# GENN0005_Flatsat_ConnectorFootprints.net
KiCad netlist of a schematic drawn in Altium Designer
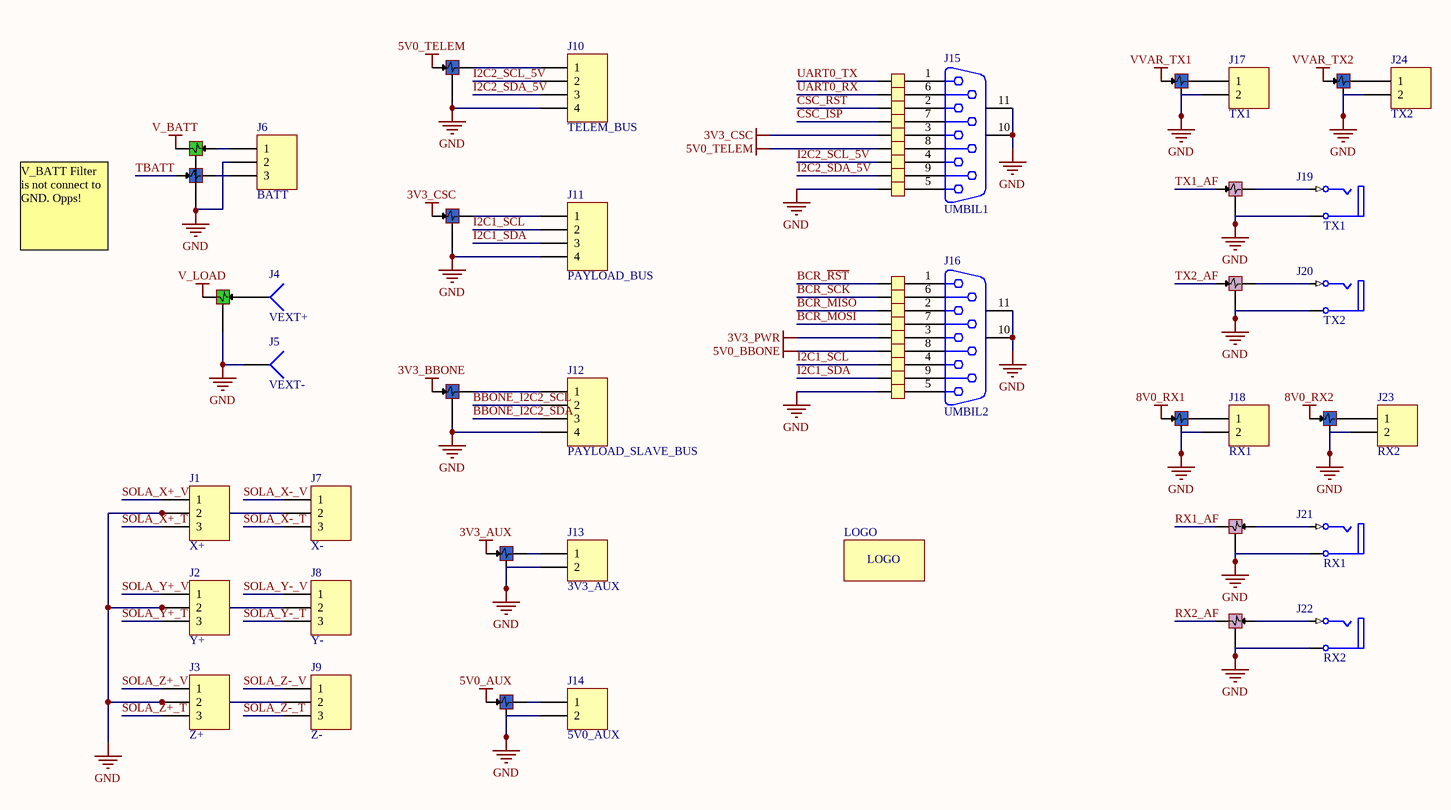
[diagram p0: GENN0005 Flatsat ConnectorFootprints.SchDoc]

(export (version "E")
  (design (tool "Eeschema 10.0.6"))
  (components
    (comp (ref "F1")
      (value "FilterSola")
      (footprint "FILTERSOLA")
      (libsource (lib "FlatBoards") (part "FilterSola"))
    )
    (comp (ref "F2")
      (value "FilterPwr")
      (footprint "FILTERPWR")
      (libsource (lib "FlatBoards") (part "FilterPwr"))
    )
    (comp (ref "F3")
      (value "FilterPwr")
      (footprint "FILTERPWR")
      (libsource (lib "FlatBoards") (part "FilterPwr"))
    )
    (comp (ref "F4")
      (value "FilterPwr")
      (footprint "FILTERPWR")
      (libsource (lib "FlatBoards") (part "FilterPwr"))
    )
    (comp (ref "F5")
      (value "FilterPwr")
      (footprint "FILTERPWR")
      (libsource (lib "FlatBoards") (part "FilterPwr"))
    )
    (comp (ref "F6")
      (value "FilterPwr")
      (footprint "FILTERPWR")
      (libsource (lib "FlatBoards") (part "FilterPwr"))
    )
    (comp (ref "F7")
      (value "FilterPwr")
      (footprint "FILTERPWR")
      (libsource (lib "FlatBoards") (part "FilterPwr"))
    )
    (comp (ref "F8")
      (value "FilterPwr")
      (footprint "FILTERPWR")
      (libsource (lib "FlatBoards") (part "FilterPwr"))
    )
    (comp (ref "F9") (value "Filter") (footprint "Filter") (libsource (lib "FlatBoards") (part "Filter")))
    (comp (ref "F10") (value "Filter") (footprint "Filter") (libsource (lib "FlatBoards") (part "Filter")))
    (comp (ref "F11") (value "Filter") (footprint "Filter") (libsource (lib "") (part "Filter_1")))
    (comp (ref "F12") (value "Filter") (footprint "Filter") (libsource (lib "") (part "Filter_1")))
    (comp (ref "F13")
      (value "FilterPwr")
      (footprint "FILTERPWR")
      (libsource (lib "FlatBoards") (part "FilterPwr"))
    )
    (comp (ref "F14")
      (value "FilterPwr")
      (footprint "FILTERPWR")
      (libsource (lib "FlatBoards") (part "FilterPwr"))
    )
    (comp (ref "F98")
      (value "FilterPwr")
      (footprint "FILTERPWR")
      (libsource (lib "FlatBoards") (part "FilterPwr"))
    )
    (comp (ref "F99")
      (value "FilterSola")
      (footprint "FILTERSOLA")
      (libsource (lib "FlatBoards") (part "FilterSola"))
    )
    (comp (ref "J1")
      (value "X+")
      (footprint "SCREW3")
      (description "Header, 3-Pin")
      (fields (field (name "PUBLISHER") "Altium Limited"))
      (libsource (lib "Miscellaneous Connectors") (part "Header 3"))
    )
    (comp (ref "J2")
      (value "Y+")
      (footprint "SCREW3")
      (description "Header, 3-Pin")
      (fields (field (name "PUBLISHER") "Altium Limited"))
      (libsource (lib "Miscellaneous Connectors") (part "Header 3"))
    )
    (comp (ref "J3")
      (value "Z+")
      (footprint "SCREW3")
      (description "Header, 3-Pin")
      (fields (field (name "PUBLISHER") "Altium Limited"))
      (libsource (lib "Miscellaneous Connectors") (part "Header 3"))
    )
    (comp (ref "J4")
      (value "VEXT+")
      (footprint "4MM_BANANA")
      (description "Socket")
      (fields (field (name "PUBLISHER") "Altium Limited"))
      (libsource (lib "Miscellaneous Connectors") (part "Socket"))
    )
    (comp (ref "J5")
      (value "VEXT-")
      (footprint "4MM_BANANA")
      (description "Socket")
      (fields (field (name "PUBLISHER") "Altium Limited"))
      (libsource (lib "Miscellaneous Connectors") (part "Socket"))
    )
    (comp (ref "J6")
      (value "BATT")
      (footprint "SCREW3")
      (description "Header, 3-Pin")
      (fields (field (name "PUBLISHER") "Altium Limited"))
      (libsource (lib "Miscellaneous Connectors") (part "Header 3"))
    )
    (comp (ref "J7")
      (value "X-")
      (footprint "SCREW3")
      (description "Header, 3-Pin")
      (fields (field (name "PUBLISHER") "Altium Limited"))
      (libsource (lib "Miscellaneous Connectors") (part "Header 3"))
    )
    (comp (ref "J8")
      (value "Y-")
      (footprint "SCREW3")
      (description "Header, 3-Pin")
      (fields (field (name "PUBLISHER") "Altium Limited"))
      (libsource (lib "Miscellaneous Connectors") (part "Header 3"))
    )
    (comp (ref "J9")
      (value "Z-")
      (footprint "SCREW3")
      (description "Header, 3-Pin")
      (fields (field (name "PUBLISHER") "Altium Limited"))
      (libsource (lib "Miscellaneous Connectors") (part "Header 3"))
    )
    (comp (ref "J10")
      (value "TELEM_BUS")
      (footprint "HDR1X4")
      (description "Header, 4-Pin")
      (fields (field (name "PUBLISHER") "Altium Limited"))
      (libsource (lib "Miscellaneous Connectors") (part "Header 4"))
    )
    (comp (ref "J11")
      (value "PAYLOAD_BUS")
      (footprint "HDR1X4")
      (description "Header, 4-Pin")
      (fields (field (name "PUBLISHER") "Altium Limited"))
      (libsource (lib "Miscellaneous Connectors") (part "Header 4"))
    )
    (comp (ref "J12")
      (value "PAYLOAD_SLAVE_BUS")
      (footprint "HDR1X4")
      (description "Header, 4-Pin")
      (fields (field (name "PUBLISHER") "Altium Limited"))
      (libsource (lib "Miscellaneous Connectors") (part "Header 4"))
    )
    (comp (ref "J13")
      (value "3V3_AUX")
      (footprint "SCREW2")
      (description "Header, 2-Pin")
      (fields (field (name "PUBLISHER") "Altium Limited"))
      (libsource (lib "Miscellaneous Connectors") (part "Header 2"))
    )
    (comp (ref "J14")
      (value "5V0_AUX")
      (footprint "SCREW2")
      (description "Header, 2-Pin")
      (fields (field (name "PUBLISHER") "Altium Limited"))
      (libsource (lib "Miscellaneous Connectors") (part "Header 2"))
    )
    (comp (ref "J15")
      (value "UMBIL1")
      (footprint "D9 - temp")
      (description "Receptacle Assembly, 9 Position, Right Angle")
      (fields (field (name "PUBLISHER") "Altium Limited"))
      (libsource (lib "Miscellaneous Connectors") (part "D Connector 9"))
    )
    (comp (ref "J16")
      (value "UMBIL2")
      (footprint "D9 - temp")
      (description "Receptacle Assembly, 9 Position, Right Angle")
      (fields (field (name "PUBLISHER") "Altium Limited"))
      (libsource (lib "Miscellaneous Connectors") (part "D Connector 9"))
    )
    (comp (ref "J17")
      (value "TX1")
      (footprint "SCREW2")
      (description "Header, 2-Pin")
      (fields (field (name "PUBLISHER") "Altium Limited"))
      (libsource (lib "Miscellaneous Connectors") (part "Header 2"))
    )
    (comp (ref "J18")
      (value "RX1")
      (footprint "SCREW2")
      (description "Header, 2-Pin")
      (fields (field (name "PUBLISHER") "Altium Limited"))
      (libsource (lib "Miscellaneous Connectors") (part "Header 2"))
    )
    (comp (ref "J19")
      (value "TX1")
      (footprint "R/A RCA")
      (description "RCA Phono Jack, Right Angle, Thru-Hole, Snap-In")
      (fields (field (name "PUBLISHER") "Altium Limited"))
      (libsource (lib "Miscellaneous Connectors") (part "RCA"))
    )
    (comp (ref "J20")
      (value "TX2")
      (footprint "R/A RCA")
      (description "RCA Phono Jack, Right Angle, Thru-Hole, Snap-In")
      (fields (field (name "PUBLISHER") "Altium Limited"))
      (libsource (lib "Miscellaneous Connectors") (part "RCA"))
    )
    (comp (ref "J21")
      (value "RX1")
      (footprint "R/A RCA")
      (description "RCA Phono Jack, Right Angle, Thru-Hole, Snap-In")
      (fields (field (name "PUBLISHER") "Altium Limited"))
      (libsource (lib "Miscellaneous Connectors") (part "RCA"))
    )
    (comp (ref "J22")
      (value "RX2")
      (footprint "R/A RCA")
      (description "RCA Phono Jack, Right Angle, Thru-Hole, Snap-In")
      (fields (field (name "PUBLISHER") "Altium Limited"))
      (libsource (lib "Miscellaneous Connectors") (part "RCA"))
    )
    (comp (ref "J23")
      (value "RX2")
      (footprint "SCREW2")
      (description "Header, 2-Pin")
      (fields (field (name "PUBLISHER") "Altium Limited"))
      (libsource (lib "Miscellaneous Connectors") (part "Header 2"))
    )
    (comp (ref "J24")
      (value "TX2")
      (footprint "SCREW2")
      (description "Header, 2-Pin")
      (fields (field (name "PUBLISHER") "Altium Limited"))
      (libsource (lib "Miscellaneous Connectors") (part "Header 2"))
    )
    (comp (ref "LOGO") (value "~") (footprint "LOGO") (libsource (lib "FlatBoards") (part "LOGO")))
    (comp (ref "P185") (value "Jumper") (footprint "Jumper") (libsource (lib "FlatBoards") (part "Jumper")))
    (comp (ref "P186") (value "Jumper") (footprint "Jumper") (libsource (lib "FlatBoards") (part "Jumper")))
    (comp (ref "P187") (value "Jumper") (footprint "Jumper") (libsource (lib "FlatBoards") (part "Jumper")))
    (comp (ref "P188") (value "Jumper") (footprint "Jumper") (libsource (lib "FlatBoards") (part "Jumper")))
    (comp (ref "P189") (value "Jumper") (footprint "Jumper") (libsource (lib "FlatBoards") (part "Jumper")))
    (comp (ref "P190") (value "Jumper") (footprint "Jumper") (libsource (lib "FlatBoards") (part "Jumper")))
    (comp (ref "P191") (value "Jumper") (footprint "Jumper") (libsource (lib "FlatBoards") (part "Jumper")))
    (comp (ref "P192") (value "Jumper") (footprint "Jumper") (libsource (lib "FlatBoards") (part "Jumper")))
    (comp (ref "P193") (value "Jumper") (footprint "Jumper") (libsource (lib "FlatBoards") (part "Jumper")))
    (comp (ref "P194") (value "Jumper") (footprint "Jumper") (libsource (lib "FlatBoards") (part "Jumper")))
    (comp (ref "P195") (value "Jumper") (footprint "Jumper") (libsource (lib "FlatBoards") (part "Jumper")))
    (comp (ref "P196") (value "Jumper") (footprint "Jumper") (libsource (lib "FlatBoards") (part "Jumper")))
    (comp (ref "P197") (value "Jumper") (footprint "Jumper") (libsource (lib "FlatBoards") (part "Jumper")))
    (comp (ref "P198") (value "Jumper") (footprint "Jumper") (libsource (lib "FlatBoards") (part "Jumper")))
    (comp (ref "P199") (value "Jumper") (footprint "Jumper") (libsource (lib "FlatBoards") (part "Jumper")))
    (comp (ref "P200") (value "Jumper") (footprint "Jumper") (libsource (lib "FlatBoards") (part "Jumper")))
    (comp (ref "P201") (value "Jumper") (footprint "Jumper") (libsource (lib "FlatBoards") (part "Jumper")))
    (comp (ref "P202") (value "Jumper") (footprint "Jumper") (libsource (lib "FlatBoards") (part "Jumper")))
  )
  (nets
    (net (code "1") (name "/BBONE_I2C2_SCL") (class "Default")
      (node (ref "J12") (pin "2") (pinfunction "2_2") (pintype "passive"))
    )
    (net (code "2") (name "/BBONE_I2C2_SDA") (class "Default")
      (node (ref "J12") (pin "3") (pinfunction "3_3") (pintype "passive"))
    )
    (net (code "3") (name "/BCR_MISO") (class "Default") (node (ref "P196") (pin "1") (pintype "passive")))
    (net (code "4") (name "/BCR_MOSI") (class "Default") (node (ref "P197") (pin "1") (pintype "passive")))
    (net (code "5") (name "/BCR_SCK") (class "Default") (node (ref "P195") (pin "1") (pintype "passive")))
    (net (code "6") (name "/BCR_~{RST}") (class "Default") (node (ref "P194") (pin "1") (pintype "passive")))
    (net (code "7") (name "/CSC_ISP") (class "Default") (node (ref "P188") (pin "1") (pintype "passive")))
    (net (code "8") (name "/CSC_RST") (class "Default") (node (ref "P187") (pin "1") (pintype "passive")))
    (net (code "9") (name "/I2C1_SCL") (class "Default")
      (node (ref "J11") (pin "2") (pinfunction "2_2") (pintype "passive"))
      (node (ref "P200") (pin "1") (pintype "passive"))
    )
    (net (code "10") (name "/I2C1_SDA") (class "Default")
      (node (ref "J11") (pin "3") (pinfunction "3_3") (pintype "passive"))
      (node (ref "P201") (pin "1") (pintype "passive"))
    )
    (net (code "11") (name "/I2C2_SCL_5V") (class "Default")
      (node (ref "J10") (pin "2") (pinfunction "2_2") (pintype "passive"))
      (node (ref "P191") (pin "1") (pintype "passive"))
    )
    (net (code "12") (name "/I2C2_SDA_5V") (class "Default")
      (node (ref "J10") (pin "3") (pinfunction "3_3") (pintype "passive"))
      (node (ref "P192") (pin "1") (pintype "passive"))
    )
    (net (code "13") (name "/RX1_AF") (class "Default") (node (ref "F11") (pin "2") (pintype "passive")))
    (net (code "14") (name "/RX2_AF") (class "Default") (node (ref "F12") (pin "2") (pintype "passive")))
    (net (code "15") (name "/SOLA_X+_T") (class "Default")
      (node (ref "J1") (pin "3") (pinfunction "3_3") (pintype "passive"))
    )
    (net (code "16") (name "/SOLA_X+_V") (class "Default")
      (node (ref "J1") (pin "1") (pinfunction "1_1") (pintype "passive"))
    )
    (net (code "17") (name "/SOLA_X-_T") (class "Default")
      (node (ref "J7") (pin "3") (pinfunction "3_3") (pintype "passive"))
    )
    (net (code "18") (name "/SOLA_X-_V") (class "Default")
      (node (ref "J7") (pin "1") (pinfunction "1_1") (pintype "passive"))
    )
    (net (code "19") (name "/SOLA_Y+_T") (class "Default")
      (node (ref "J2") (pin "3") (pinfunction "3_3") (pintype "passive"))
    )
    (net (code "20") (name "/SOLA_Y+_V") (class "Default")
      (node (ref "J2") (pin "1") (pinfunction "1_1") (pintype "passive"))
    )
    (net (code "21") (name "/SOLA_Y-_T") (class "Default")
      (node (ref "J8") (pin "3") (pinfunction "3_3") (pintype "passive"))
    )
    (net (code "22") (name "/SOLA_Y-_V") (class "Default")
      (node (ref "J8") (pin "1") (pinfunction "1_1") (pintype "passive"))
    )
    (net (code "23") (name "/SOLA_Z+_T") (class "Default")
      (node (ref "J3") (pin "3") (pinfunction "3_3") (pintype "passive"))
    )
    (net (code "24") (name "/SOLA_Z+_V") (class "Default")
      (node (ref "J3") (pin "1") (pinfunction "1_1") (pintype "passive"))
    )
    (net (code "25") (name "/SOLA_Z-_T") (class "Default")
      (node (ref "J9") (pin "3") (pinfunction "3_3") (pintype "passive"))
    )
    (net (code "26") (name "/SOLA_Z-_V") (class "Default")
      (node (ref "J9") (pin "1") (pinfunction "1_1") (pintype "passive"))
    )
    (net (code "27") (name "/TBATT") (class "Default") (node (ref "F98") (pin "1") (pintype "passive")))
    (net (code "28") (name "/TX1_AF") (class "Default") (node (ref "F9") (pin "1") (pintype "passive")))
    (net (code "29") (name "/TX2_AF") (class "Default") (node (ref "F10") (pin "1") (pintype "passive")))
    (net (code "30") (name "/UART0_RX") (class "Default") (node (ref "P186") (pin "1") (pintype "passive")))
    (net (code "31") (name "/UART0_TX") (class "Default") (node (ref "P185") (pin "1") (pintype "passive")))
    (net (code "32") (name "3V3_AUX") (class "Default") (node (ref "F5") (pin "1") (pintype "passive")))
    (net (code "33") (name "3V3_BBONE") (class "Default") (node (ref "F4") (pin "1") (pintype "passive")))
    (net (code "34") (name "3V3_CSC") (class "Default")
      (node (ref "F3") (pin "1") (pintype "passive"))
      (node (ref "P189") (pin "1") (pintype "passive"))
    )
    (net (code "35") (name "3V3_PWR") (class "Default") (node (ref "P198") (pin "1") (pintype "passive")))
    (net (code "36") (name "5V0_AUX") (class "Default") (node (ref "F6") (pin "1") (pintype "passive")))
    (net (code "37") (name "5V0_BBONE") (class "Default") (node (ref "P199") (pin "1") (pintype "passive")))
    (net (code "38") (name "5V0_TELEM") (class "Default")
      (node (ref "F2") (pin "1") (pintype "passive"))
      (node (ref "P190") (pin "1") (pintype "passive"))
    )
    (net (code "39") (name "8V0_RX1") (class "Default") (node (ref "F8") (pin "1") (pintype "passive")))
    (net (code "40") (name "8V0_RX2") (class "Default") (node (ref "F13") (pin "1") (pintype "passive")))
    (net (code "41") (name "GND") (class "Default")
      (node (ref "F1") (pin "3") (pintype "passive"))
      (node (ref "F10") (pin "3") (pintype "passive"))
      (node (ref "F11") (pin "3") (pintype "passive"))
      (node (ref "F12") (pin "3") (pintype "passive"))
      (node (ref "F13") (pin "3") (pintype "passive"))
      (node (ref "F14") (pin "3") (pintype "passive"))
      (node (ref "F2") (pin "3") (pintype "passive"))
      (node (ref "F3") (pin "3") (pintype "passive"))
      (node (ref "F4") (pin "3") (pintype "passive"))
      (node (ref "F5") (pin "3") (pintype "passive"))
      (node (ref "F6") (pin "3") (pintype "passive"))
      (node (ref "F7") (pin "3") (pintype "passive"))
      (node (ref "F8") (pin "3") (pintype "passive"))
      (node (ref "F9") (pin "3") (pintype "passive"))
      (node (ref "F98") (pin "3") (pintype "passive"))
      (node (ref "J1") (pin "2") (pinfunction "2_2") (pintype "passive"))
      (node (ref "J10") (pin "4") (pinfunction "4_4") (pintype "passive"))
      (node (ref "J11") (pin "4") (pinfunction "4_4") (pintype "passive"))
      (node (ref "J12") (pin "4") (pinfunction "4_4") (pintype "passive"))
      (node (ref "J13") (pin "2") (pinfunction "2_2") (pintype "passive"))
      (node (ref "J14") (pin "2") (pinfunction "2_2") (pintype "passive"))
      (node (ref "J15") (pin "10") (pinfunction "MH1_10") (pintype "passive"))
      (node (ref "J15") (pin "11") (pinfunction "MH2_11") (pintype "passive"))
      (node (ref "J16") (pin "10") (pinfunction "MH1_10") (pintype "passive"))
      (node (ref "J16") (pin "11") (pinfunction "MH2_11") (pintype "passive"))
      (node (ref "J17") (pin "2") (pinfunction "2_2") (pintype "passive"))
      (node (ref "J18") (pin "2") (pinfunction "2_2") (pintype "passive"))
      (node (ref "J19") (pin "1A") (pinfunction "Ground_1A") (pintype "power_in"))
      (node (ref "J2") (pin "2") (pinfunction "2_2") (pintype "passive"))
      (node (ref "J20") (pin "1A") (pinfunction "Ground_1A") (pintype "power_in"))
      (node (ref "J21") (pin "1A") (pinfunction "Ground_1A") (pintype "power_in"))
      (node (ref "J22") (pin "1A") (pinfunction "Ground_1A") (pintype "power_in"))
      (node (ref "J23") (pin "2") (pinfunction "2_2") (pintype "passive"))
      (node (ref "J24") (pin "2") (pinfunction "2_2") (pintype "passive"))
      (node (ref "J3") (pin "2") (pinfunction "2_2") (pintype "passive"))
      (node (ref "J5") (pin "1") (pinfunction "1_1") (pintype "passive"))
      (node (ref "J6") (pin "2") (pinfunction "2_2") (pintype "passive"))
      (node (ref "J7") (pin "2") (pinfunction "2_2") (pintype "passive"))
      (node (ref "J8") (pin "2") (pinfunction "2_2") (pintype "passive"))
      (node (ref "J9") (pin "2") (pinfunction "2_2") (pintype "passive"))
      (node (ref "P193") (pin "1") (pintype "passive"))
      (node (ref "P202") (pin "1") (pintype "passive"))
    )
    (net (code "42") (name "Net-(F1-Pad1)") (class "Default")
      (node (ref "F1") (pin "1") (pintype "passive"))
      (node (ref "J4") (pin "1") (pinfunction "1_1") (pintype "passive"))
    )
    (net (code "43") (name "Net-(F2-Pad2)") (class "Default")
      (node (ref "F2") (pin "2") (pintype "passive"))
      (node (ref "J10") (pin "1") (pinfunction "1_1") (pintype "passive"))
    )
    (net (code "44") (name "Net-(F3-Pad2)") (class "Default")
      (node (ref "F3") (pin "2") (pintype "passive"))
      (node (ref "J11") (pin "1") (pinfunction "1_1") (pintype "passive"))
    )
    (net (code "45") (name "Net-(F4-Pad2)") (class "Default")
      (node (ref "F4") (pin "2") (pintype "passive"))
      (node (ref "J12") (pin "1") (pinfunction "1_1") (pintype "passive"))
    )
    (net (code "46") (name "Net-(F5-Pad2)") (class "Default")
      (node (ref "F5") (pin "2") (pintype "passive"))
      (node (ref "J13") (pin "1") (pinfunction "1_1") (pintype "passive"))
    )
    (net (code "47") (name "Net-(F6-Pad2)") (class "Default")
      (node (ref "F6") (pin "2") (pintype "passive"))
      (node (ref "J14") (pin "1") (pinfunction "1_1") (pintype "passive"))
    )
    (net (code "48") (name "Net-(F7-Pad2)") (class "Default")
      (node (ref "F7") (pin "2") (pintype "passive"))
      (node (ref "J17") (pin "1") (pinfunction "1_1") (pintype "passive"))
    )
    (net (code "49") (name "Net-(F8-Pad2)") (class "Default")
      (node (ref "F8") (pin "2") (pintype "passive"))
      (node (ref "J18") (pin "1") (pinfunction "1_1") (pintype "passive"))
    )
    (net (code "50") (name "Net-(F13-Pad2)") (class "Default")
      (node (ref "F13") (pin "2") (pintype "passive"))
      (node (ref "J23") (pin "1") (pinfunction "1_1") (pintype "passive"))
    )
    (net (code "51") (name "Net-(F14-Pad2)") (class "Default")
      (node (ref "F14") (pin "2") (pintype "passive"))
      (node (ref "J24") (pin "1") (pinfunction "1_1") (pintype "passive"))
    )
    (net (code "52") (name "Net-(F98-Pad2)") (class "Default")
      (node (ref "F98") (pin "2") (pintype "passive"))
      (node (ref "J6") (pin "3") (pinfunction "3_3") (pintype "passive"))
    )
    (net (code "53") (name "Net-(F99-Pad1)") (class "Default")
      (node (ref "F99") (pin "1") (pintype "passive"))
      (node (ref "J6") (pin "1") (pinfunction "1_1") (pintype "passive"))
    )
    (net (code "54") (name "Net-(J15-Pad1)") (class "Default")
      (node (ref "J15") (pin "1") (pinfunction "1_1") (pintype "passive"))
      (node (ref "P185") (pin "2") (pintype "passive"))
    )
    (net (code "55") (name "Net-(J15-Pad2)") (class "Default")
      (node (ref "J15") (pin "2") (pinfunction "2_2") (pintype "passive"))
      (node (ref "P187") (pin "2") (pintype "passive"))
    )
    (net (code "56") (name "Net-(J15-Pad3)") (class "Default")
      (node (ref "J15") (pin "3") (pinfunction "3_3") (pintype "passive"))
      (node (ref "P189") (pin "2") (pintype "passive"))
    )
    (net (code "57") (name "Net-(J15-Pad4)") (class "Default")
      (node (ref "J15") (pin "4") (pinfunction "4_4") (pintype "passive"))
      (node (ref "P191") (pin "2") (pintype "passive"))
    )
    (net (code "58") (name "Net-(J15-Pad5)") (class "Default")
      (node (ref "J15") (pin "5") (pinfunction "5_5") (pintype "passive"))
      (node (ref "P193") (pin "2") (pintype "passive"))
    )
    (net (code "59") (name "Net-(J15-Pad6)") (class "Default")
      (node (ref "J15") (pin "6") (pinfunction "6_6") (pintype "passive"))
      (node (ref "P186") (pin "2") (pintype "passive"))
    )
    (net (code "60") (name "Net-(J15-Pad7)") (class "Default")
      (node (ref "J15") (pin "7") (pinfunction "7_7") (pintype "passive"))
      (node (ref "P188") (pin "2") (pintype "passive"))
    )
    (net (code "61") (name "Net-(J15-Pad8)") (class "Default")
      (node (ref "J15") (pin "8") (pinfunction "8_8") (pintype "passive"))
      (node (ref "P190") (pin "2") (pintype "passive"))
    )
    (net (code "62") (name "Net-(J15-Pad9)") (class "Default")
      (node (ref "J15") (pin "9") (pinfunction "9_9") (pintype "passive"))
      (node (ref "P192") (pin "2") (pintype "passive"))
    )
    (net (code "63") (name "Net-(J16-Pad1)") (class "Default")
      (node (ref "J16") (pin "1") (pinfunction "1_1") (pintype "passive"))
      (node (ref "P194") (pin "2") (pintype "passive"))
    )
    (net (code "64") (name "Net-(J16-Pad2)") (class "Default")
      (node (ref "J16") (pin "2") (pinfunction "2_2") (pintype "passive"))
      (node (ref "P196") (pin "2") (pintype "passive"))
    )
    (net (code "65") (name "Net-(J16-Pad3)") (class "Default")
      (node (ref "J16") (pin "3") (pinfunction "3_3") (pintype "passive"))
      (node (ref "P198") (pin "2") (pintype "passive"))
    )
    (net (code "66") (name "Net-(J16-Pad4)") (class "Default")
      (node (ref "J16") (pin "4") (pinfunction "4_4") (pintype "passive"))
      (node (ref "P200") (pin "2") (pintype "passive"))
    )
    (net (code "67") (name "Net-(J16-Pad5)") (class "Default")
      (node (ref "J16") (pin "5") (pinfunction "5_5") (pintype "passive"))
      (node (ref "P202") (pin "2") (pintype "passive"))
    )
    (net (code "68") (name "Net-(J16-Pad6)") (class "Default")
      (node (ref "J16") (pin "6") (pinfunction "6_6") (pintype "passive"))
      (node (ref "P195") (pin "2") (pintype "passive"))
    )
    (net (code "69") (name "Net-(J16-Pad7)") (class "Default")
      (node (ref "J16") (pin "7") (pinfunction "7_7") (pintype "passive"))
      (node (ref "P197") (pin "2") (pintype "passive"))
    )
    (net (code "70") (name "Net-(J16-Pad8)") (class "Default")
      (node (ref "J16") (pin "8") (pinfunction "8_8") (pintype "passive"))
      (node (ref "P199") (pin "2") (pintype "passive"))
    )
    (net (code "71") (name "Net-(J16-Pad9)") (class "Default")
      (node (ref "J16") (pin "9") (pinfunction "9_9") (pintype "passive"))
      (node (ref "P201") (pin "2") (pintype "passive"))
    )
    (net (code "72") (name "Net-(J19-Signal)") (class "Default")
      (node (ref "F9") (pin "2") (pintype "passive"))
      (node (ref "J19") (pin "2B") (pinfunction "Signal_2B") (pintype "input"))
    )
    (net (code "73") (name "Net-(J20-Signal)") (class "Default")
      (node (ref "F10") (pin "2") (pintype "passive"))
      (node (ref "J20") (pin "2B") (pinfunction "Signal_2B") (pintype "input"))
    )
    (net (code "74") (name "Net-(J21-Signal)") (class "Default")
      (node (ref "F11") (pin "1") (pintype "passive"))
      (node (ref "J21") (pin "2B") (pinfunction "Signal_2B") (pintype "input"))
    )
    (net (code "75") (name "Net-(J22-Signal)") (class "Default")
      (node (ref "F12") (pin "1") (pintype "passive"))
      (node (ref "J22") (pin "2B") (pinfunction "Signal_2B") (pintype "input"))
    )
    (net (code "76") (name "VVAR_TX1") (class "Default") (node (ref "F7") (pin "1") (pintype "passive")))
    (net (code "77") (name "VVAR_TX2") (class "Default") (node (ref "F14") (pin "1") (pintype "passive")))
    (net (code "78") (name "V_BATT") (class "Default") (node (ref "F99") (pin "2") (pintype "passive")))
    (net (code "79") (name "V_LOAD") (class "Default") (node (ref "F1") (pin "2") (pintype "passive")))
    (net (code "80") (name "unconnected-(F99-Pad3)") (class "Default")
      (node (ref "F99") (pin "3") (pintype "passive"))
    )
  )
)
